# MCU.net
KiCad netlist of a schematic drawn in Altium Designer
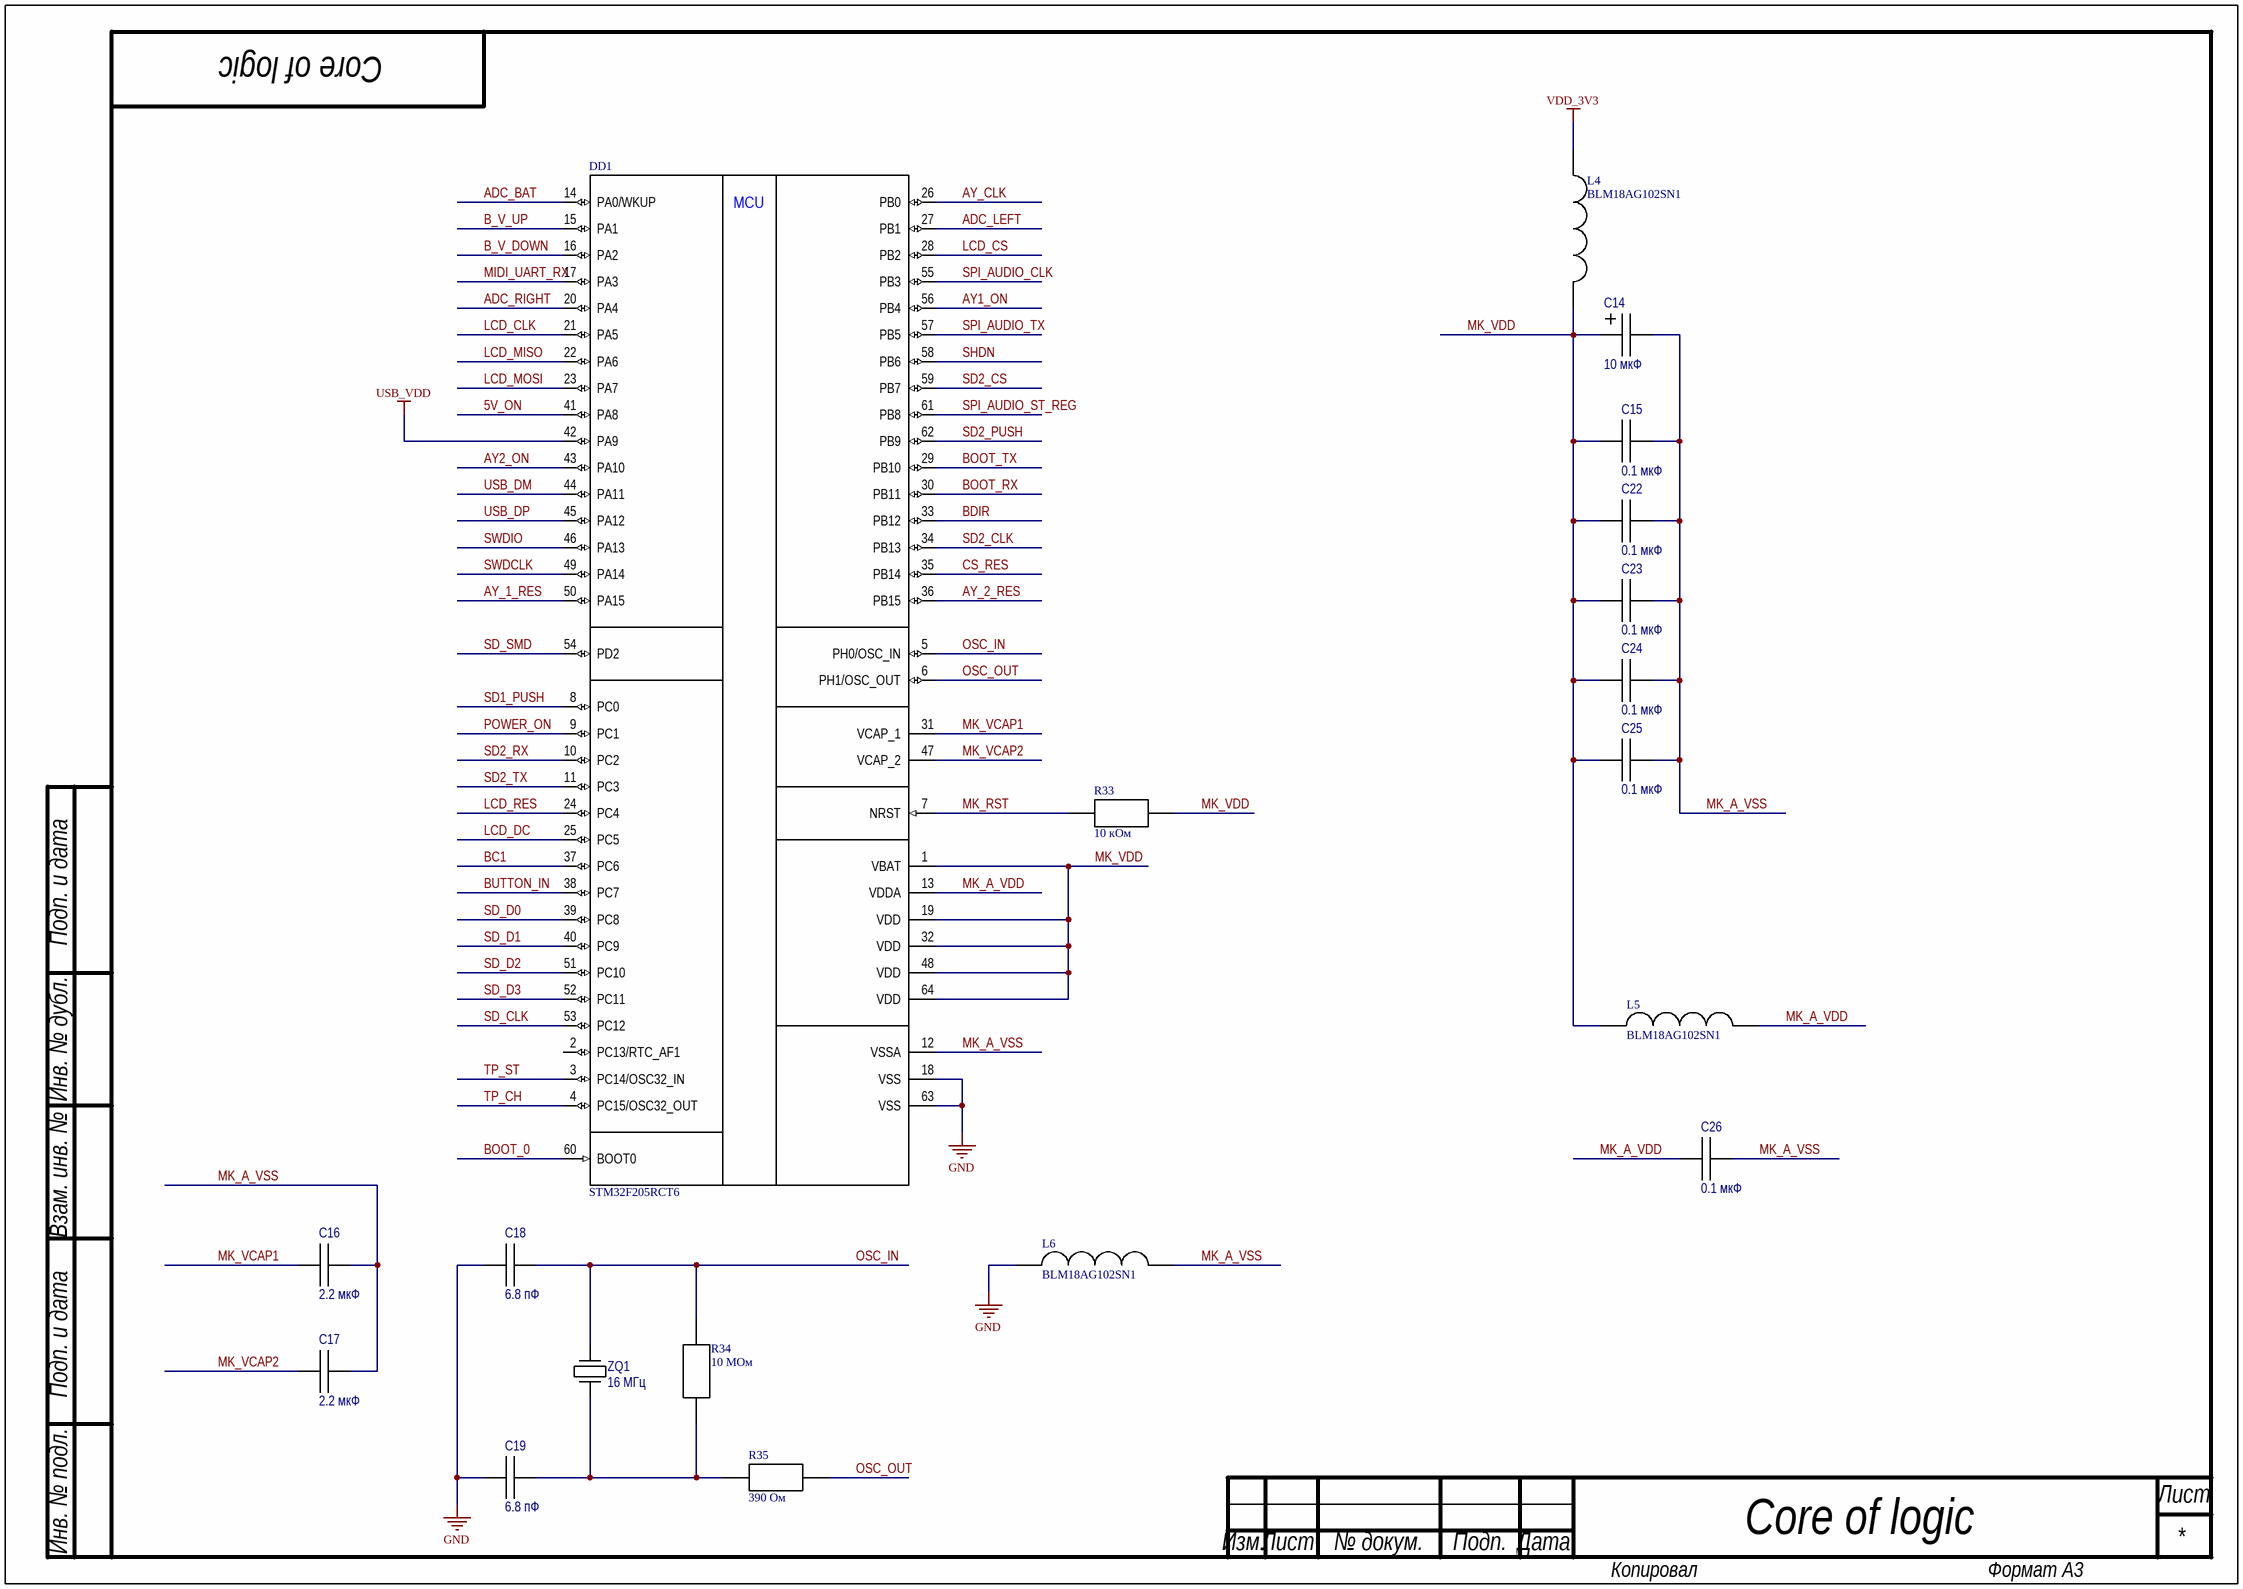
[diagram p0: MCU.SchDoc]

(export (version "E")
  (design (tool "Eeschema 10.0.6"))
  (components
    (comp (ref "C14")
      (value "10 мкФ")
      (footprint "C TAN_C")
      (description "SMD Tantalium Capacitor C")
      (fields
        (field (name "TOLERANCE") "/Укажите допуск в процентах/")
        (field (name "MANUFACTURER") "/Укажите компанию-производителя/")
      )
      (libsource (lib "my_lib") (part "CAP TAN_C"))
    )
    (comp (ref "C15")
      (value "0.1 мкФ")
      (footprint "C 1206")
      (description "SMD Capacitor 1206")
      (fields
        (field (name "TOLERANCE") "/Укажите допуск в процентах/")
        (field (name "MANUFACTURER") "/Укажите компанию-производителя/")
      )
      (libsource (lib "my_lib") (part "CAP 1206"))
    )
    (comp (ref "C16")
      (value "2.2 мкФ")
      (footprint "C 1206")
      (description "SMD Capacitor 1206")
      (fields
        (field (name "TOLERANCE") "/Укажите допуск в процентах/")
        (field (name "MANUFACTURER") "/Укажите компанию-производителя/")
      )
      (libsource (lib "my_lib") (part "CAP 1206"))
    )
    (comp (ref "C17")
      (value "2.2 мкФ")
      (footprint "C 1206")
      (description "SMD Capacitor 1206")
      (fields
        (field (name "TOLERANCE") "/Укажите допуск в процентах/")
        (field (name "MANUFACTURER") "/Укажите компанию-производителя/")
      )
      (libsource (lib "my_lib") (part "CAP 1206"))
    )
    (comp (ref "C18")
      (value "6.8 пФ")
      (footprint "C 1206")
      (description "SMD Capacitor 1206")
      (fields
        (field (name "TOLERANCE") "/Укажите допуск в процентах/")
        (field (name "MANUFACTURER") "/Укажите компанию-производителя/")
      )
      (libsource (lib "my_lib") (part "CAP 1206"))
    )
    (comp (ref "C19")
      (value "6.8 пФ")
      (footprint "C 1206")
      (description "SMD Capacitor 1206")
      (fields
        (field (name "TOLERANCE") "/Укажите допуск в процентах/")
        (field (name "MANUFACTURER") "/Укажите компанию-производителя/")
      )
      (libsource (lib "my_lib") (part "CAP 1206"))
    )
    (comp (ref "C22")
      (value "0.1 мкФ")
      (footprint "C 1206")
      (description "SMD Capacitor 1206")
      (fields
        (field (name "TOLERANCE") "/Укажите допуск в процентах/")
        (field (name "MANUFACTURER") "/Укажите компанию-производителя/")
      )
      (libsource (lib "my_lib") (part "CAP 1206"))
    )
    (comp (ref "C23")
      (value "0.1 мкФ")
      (footprint "C 1206")
      (description "SMD Capacitor 1206")
      (fields
        (field (name "TOLERANCE") "/Укажите допуск в процентах/")
        (field (name "MANUFACTURER") "/Укажите компанию-производителя/")
      )
      (libsource (lib "my_lib") (part "CAP 1206"))
    )
    (comp (ref "C24")
      (value "0.1 мкФ")
      (footprint "C 1206")
      (description "SMD Capacitor 1206")
      (fields
        (field (name "TOLERANCE") "/Укажите допуск в процентах/")
        (field (name "MANUFACTURER") "/Укажите компанию-производителя/")
      )
      (libsource (lib "my_lib") (part "CAP 1206"))
    )
    (comp (ref "C25")
      (value "0.1 мкФ")
      (footprint "C 1206")
      (description "SMD Capacitor 1206")
      (fields
        (field (name "TOLERANCE") "/Укажите допуск в процентах/")
        (field (name "MANUFACTURER") "/Укажите компанию-производителя/")
      )
      (libsource (lib "my_lib") (part "CAP 1206"))
    )
    (comp (ref "C26")
      (value "0.1 мкФ")
      (footprint "C 1206")
      (description "SMD Capacitor 1206")
      (fields
        (field (name "TOLERANCE") "/Укажите допуск в процентах/")
        (field (name "MANUFACTURER") "/Укажите компанию-производителя/")
      )
      (libsource (lib "my_lib") (part "CAP 1206"))
    )
    (comp (ref "DD1")
      (value "STM32F205RCT6")
      (footprint "LQFP64")
      (libsource (lib "my_lib") (part "STM32F205RCT6"))
    )
    (comp (ref "L4")
      (value "BLM18AG102SN1")
      (footprint "FB 0603")
      (libsource (lib "my_lib") (part "BLM18AG102SN1"))
    )
    (comp (ref "L5")
      (value "BLM18AG102SN1")
      (footprint "FB 0603")
      (libsource (lib "my_lib") (part "BLM18AG102SN1"))
    )
    (comp (ref "L6")
      (value "BLM18AG102SN1")
      (footprint "FB 0603")
      (libsource (lib "my_lib") (part "BLM18AG102SN1"))
    )
    (comp (ref "R33") (value "10 кОм") (footprint "RES 0805") (libsource (lib "my_lib") (part "RES 0805")))
    (comp (ref "R34") (value "10 МОм") (footprint "RES 0805") (libsource (lib "my_lib") (part "RES 0805")))
    (comp (ref "R35") (value "390 Ом") (footprint "RES 0805") (libsource (lib "my_lib") (part "RES 0805")))
    (comp (ref "ZQ1")
      (value "16 МГц")
      (footprint "NX3225SA")
      (description "QUARTZ CRYSTAL")
      (fields (field (name "MANUFACTURER") "NDK") (field (name "Comment") "NX3225SA-16.000M-STD-CRS-2"))
      (libsource (lib "my_lib") (part "NX3225SA-16.000M-STD-CRS-2"))
    )
  )
  (nets
    (net (code "1") (name "/5V_ON") (class "Default")
      (node (ref "DD1") (pin "41") (pinfunction "PA8_41") (pintype "bidirectional"))
    )
    (net (code "2") (name "/ADC_BAT") (class "Default")
      (node (ref "DD1") (pin "14") (pinfunction "PA0/WKUP_14") (pintype "bidirectional"))
    )
    (net (code "3") (name "/ADC_LEFT") (class "Default")
      (node (ref "DD1") (pin "27") (pinfunction "PB1_27") (pintype "bidirectional"))
    )
    (net (code "4") (name "/ADC_RIGHT") (class "Default")
      (node (ref "DD1") (pin "20") (pinfunction "PA4_20") (pintype "bidirectional"))
    )
    (net (code "5") (name "/AY1_ON") (class "Default")
      (node (ref "DD1") (pin "56") (pinfunction "PB4_56") (pintype "bidirectional"))
    )
    (net (code "6") (name "/AY2_ON") (class "Default")
      (node (ref "DD1") (pin "43") (pinfunction "PA10_43") (pintype "bidirectional"))
    )
    (net (code "7") (name "/AY_1_RES") (class "Default")
      (node (ref "DD1") (pin "50") (pinfunction "PA15_50") (pintype "bidirectional"))
    )
    (net (code "8") (name "/AY_2_RES") (class "Default")
      (node (ref "DD1") (pin "36") (pinfunction "PB15_36") (pintype "bidirectional"))
    )
    (net (code "9") (name "/AY_CLK") (class "Default")
      (node (ref "DD1") (pin "26") (pinfunction "PB0_26") (pintype "bidirectional"))
    )
    (net (code "10") (name "/BC1") (class "Default")
      (node (ref "DD1") (pin "37") (pinfunction "PC6_37") (pintype "bidirectional"))
    )
    (net (code "11") (name "/BDIR") (class "Default")
      (node (ref "DD1") (pin "33") (pinfunction "PB12_33") (pintype "bidirectional"))
    )
    (net (code "12") (name "/BOOT_0") (class "Default")
      (node (ref "DD1") (pin "60") (pinfunction "BOOT0_60") (pintype "input"))
    )
    (net (code "13") (name "/BOOT_RX") (class "Default")
      (node (ref "DD1") (pin "30") (pinfunction "PB11_30") (pintype "bidirectional"))
    )
    (net (code "14") (name "/BOOT_TX") (class "Default")
      (node (ref "DD1") (pin "29") (pinfunction "PB10_29") (pintype "bidirectional"))
    )
    (net (code "15") (name "/BUTTON_IN") (class "Default")
      (node (ref "DD1") (pin "38") (pinfunction "PC7_38") (pintype "bidirectional"))
    )
    (net (code "16") (name "/B_V_DOWN") (class "Default")
      (node (ref "DD1") (pin "16") (pinfunction "PA2_16") (pintype "bidirectional"))
    )
    (net (code "17") (name "/B_V_UP") (class "Default")
      (node (ref "DD1") (pin "15") (pinfunction "PA1_15") (pintype "bidirectional"))
    )
    (net (code "18") (name "/CS_RES") (class "Default")
      (node (ref "DD1") (pin "35") (pinfunction "PB14_35") (pintype "bidirectional"))
    )
    (net (code "19") (name "/LCD_CLK") (class "Default")
      (node (ref "DD1") (pin "21") (pinfunction "PA5_21") (pintype "bidirectional"))
    )
    (net (code "20") (name "/LCD_CS") (class "Default")
      (node (ref "DD1") (pin "28") (pinfunction "PB2_28") (pintype "bidirectional"))
    )
    (net (code "21") (name "/LCD_DC") (class "Default")
      (node (ref "DD1") (pin "25") (pinfunction "PC5_25") (pintype "bidirectional"))
    )
    (net (code "22") (name "/LCD_MISO") (class "Default")
      (node (ref "DD1") (pin "22") (pinfunction "PA6_22") (pintype "bidirectional"))
    )
    (net (code "23") (name "/LCD_MOSI") (class "Default")
      (node (ref "DD1") (pin "23") (pinfunction "PA7_23") (pintype "bidirectional"))
    )
    (net (code "24") (name "/LCD_RES") (class "Default")
      (node (ref "DD1") (pin "24") (pinfunction "PC4_24") (pintype "bidirectional"))
    )
    (net (code "25") (name "/MIDI_UART_RX") (class "Default")
      (node (ref "DD1") (pin "17") (pinfunction "PA3_17") (pintype "bidirectional"))
    )
    (net (code "26") (name "/MK_A_VDD") (class "Default")
      (node (ref "C26") (pin "1") (pinfunction "1_1") (pintype "passive"))
      (node (ref "DD1") (pin "13") (pinfunction "VDDA_13") (pintype "power_in"))
      (node (ref "L5") (pin "2") (pinfunction "2_2") (pintype "passive"))
    )
    (net (code "27") (name "/MK_A_VSS") (class "Default")
      (node (ref "C14") (pin "2") (pinfunction "2_2") (pintype "passive"))
      (node (ref "C15") (pin "2") (pinfunction "2_2") (pintype "passive"))
      (node (ref "C16") (pin "2") (pinfunction "2_2") (pintype "passive"))
      (node (ref "C17") (pin "2") (pinfunction "2_2") (pintype "passive"))
      (node (ref "C22") (pin "2") (pinfunction "2_2") (pintype "passive"))
      (node (ref "C23") (pin "2") (pinfunction "2_2") (pintype "passive"))
      (node (ref "C24") (pin "2") (pinfunction "2_2") (pintype "passive"))
      (node (ref "C25") (pin "2") (pinfunction "2_2") (pintype "passive"))
      (node (ref "C26") (pin "2") (pinfunction "2_2") (pintype "passive"))
      (node (ref "DD1") (pin "12") (pinfunction "VSSA_12") (pintype "power_in"))
      (node (ref "L6") (pin "2") (pinfunction "2_2") (pintype "passive"))
    )
    (net (code "28") (name "/MK_RST") (class "Default")
      (node (ref "DD1") (pin "7") (pinfunction "NRST_7") (pintype "input"))
      (node (ref "R33") (pin "1") (pinfunction "1_1") (pintype "passive"))
    )
    (net (code "29") (name "/MK_VCAP1") (class "Default")
      (node (ref "C16") (pin "1") (pinfunction "1_1") (pintype "passive"))
      (node (ref "DD1") (pin "31") (pinfunction "VCAP_1_31") (pintype "power_in"))
    )
    (net (code "30") (name "/MK_VCAP2") (class "Default")
      (node (ref "C17") (pin "1") (pinfunction "1_1") (pintype "passive"))
      (node (ref "DD1") (pin "47") (pinfunction "VCAP_2_47") (pintype "power_in"))
    )
    (net (code "31") (name "/MK_VDD") (class "Default")
      (node (ref "C14") (pin "1") (pinfunction "1_1") (pintype "passive"))
      (node (ref "C15") (pin "1") (pinfunction "1_1") (pintype "passive"))
      (node (ref "C22") (pin "1") (pinfunction "1_1") (pintype "passive"))
      (node (ref "C23") (pin "1") (pinfunction "1_1") (pintype "passive"))
      (node (ref "C24") (pin "1") (pinfunction "1_1") (pintype "passive"))
      (node (ref "C25") (pin "1") (pinfunction "1_1") (pintype "passive"))
      (node (ref "DD1") (pin "1") (pinfunction "VBAT_1") (pintype "power_in"))
      (node (ref "DD1") (pin "19") (pinfunction "VDD_19") (pintype "power_in"))
      (node (ref "DD1") (pin "32") (pinfunction "VDD_32") (pintype "power_in"))
      (node (ref "DD1") (pin "48") (pinfunction "VDD_48") (pintype "power_in"))
      (node (ref "DD1") (pin "64") (pinfunction "VDD_64") (pintype "power_in"))
      (node (ref "L4") (pin "2") (pinfunction "2_2") (pintype "passive"))
      (node (ref "L5") (pin "1") (pinfunction "1_1") (pintype "passive"))
      (node (ref "R33") (pin "2") (pinfunction "2_2") (pintype "passive"))
    )
    (net (code "32") (name "/OSC_IN") (class "Default")
      (node (ref "C18") (pin "2") (pinfunction "2_2") (pintype "passive"))
      (node (ref "DD1") (pin "5") (pinfunction "PH0/OSC_IN_5") (pintype "bidirectional"))
      (node (ref "R34") (pin "2") (pinfunction "2_2") (pintype "passive"))
      (node (ref "ZQ1") (pin "3") (pinfunction "XO_3") (pintype "passive"))
    )
    (net (code "33") (name "/OSC_OUT") (class "Default")
      (node (ref "DD1") (pin "6") (pinfunction "PH1/OSC_OUT_6") (pintype "bidirectional"))
      (node (ref "R35") (pin "2") (pinfunction "2_2") (pintype "passive"))
    )
    (net (code "34") (name "/POWER_ON") (class "Default")
      (node (ref "DD1") (pin "9") (pinfunction "PC1_9") (pintype "bidirectional"))
    )
    (net (code "35") (name "/SD1_PUSH") (class "Default")
      (node (ref "DD1") (pin "8") (pinfunction "PC0_8") (pintype "bidirectional"))
    )
    (net (code "36") (name "/SD2_CLK") (class "Default")
      (node (ref "DD1") (pin "34") (pinfunction "PB13_34") (pintype "bidirectional"))
    )
    (net (code "37") (name "/SD2_CS") (class "Default")
      (node (ref "DD1") (pin "59") (pinfunction "PB7_59") (pintype "bidirectional"))
    )
    (net (code "38") (name "/SD2_PUSH") (class "Default")
      (node (ref "DD1") (pin "62") (pinfunction "PB9_62") (pintype "bidirectional"))
    )
    (net (code "39") (name "/SD2_RX") (class "Default")
      (node (ref "DD1") (pin "10") (pinfunction "PC2_10") (pintype "bidirectional"))
    )
    (net (code "40") (name "/SD2_TX") (class "Default")
      (node (ref "DD1") (pin "11") (pinfunction "PC3_11") (pintype "bidirectional"))
    )
    (net (code "41") (name "/SD_CLK") (class "Default")
      (node (ref "DD1") (pin "53") (pinfunction "PC12_53") (pintype "bidirectional"))
    )
    (net (code "42") (name "/SD_D0") (class "Default")
      (node (ref "DD1") (pin "39") (pinfunction "PC8_39") (pintype "bidirectional"))
    )
    (net (code "43") (name "/SD_D1") (class "Default")
      (node (ref "DD1") (pin "40") (pinfunction "PC9_40") (pintype "bidirectional"))
    )
    (net (code "44") (name "/SD_D2") (class "Default")
      (node (ref "DD1") (pin "51") (pinfunction "PC10_51") (pintype "bidirectional"))
    )
    (net (code "45") (name "/SD_D3") (class "Default")
      (node (ref "DD1") (pin "52") (pinfunction "PC11_52") (pintype "bidirectional"))
    )
    (net (code "46") (name "/SD_SMD") (class "Default")
      (node (ref "DD1") (pin "54") (pinfunction "PD2_54") (pintype "bidirectional"))
    )
    (net (code "47") (name "/SHDN") (class "Default")
      (node (ref "DD1") (pin "58") (pinfunction "PB6_58") (pintype "bidirectional"))
    )
    (net (code "48") (name "/SPI_AUDIO_CLK") (class "Default")
      (node (ref "DD1") (pin "55") (pinfunction "PB3_55") (pintype "bidirectional"))
    )
    (net (code "49") (name "/SPI_AUDIO_ST_REG") (class "Default")
      (node (ref "DD1") (pin "61") (pinfunction "PB8_61") (pintype "bidirectional"))
    )
    (net (code "50") (name "/SPI_AUDIO_TX") (class "Default")
      (node (ref "DD1") (pin "57") (pinfunction "PB5_57") (pintype "bidirectional"))
    )
    (net (code "51") (name "/SWDCLK") (class "Default")
      (node (ref "DD1") (pin "49") (pinfunction "PA14_49") (pintype "bidirectional"))
    )
    (net (code "52") (name "/SWDIO") (class "Default")
      (node (ref "DD1") (pin "46") (pinfunction "PA13_46") (pintype "bidirectional"))
    )
    (net (code "53") (name "/TP_CH") (class "Default")
      (node (ref "DD1") (pin "4") (pinfunction "PC15/OSC32_OUT_4") (pintype "bidirectional"))
    )
    (net (code "54") (name "/TP_ST") (class "Default")
      (node (ref "DD1") (pin "3") (pinfunction "PC14/OSC32_IN_3") (pintype "bidirectional"))
    )
    (net (code "55") (name "/USB_DM") (class "Default")
      (node (ref "DD1") (pin "44") (pinfunction "PA11_44") (pintype "bidirectional"))
    )
    (net (code "56") (name "/USB_DP") (class "Default")
      (node (ref "DD1") (pin "45") (pinfunction "PA12_45") (pintype "bidirectional"))
    )
    (net (code "57") (name "GND") (class "Default")
      (node (ref "C18") (pin "1") (pinfunction "1_1") (pintype "passive"))
      (node (ref "C19") (pin "1") (pinfunction "1_1") (pintype "passive"))
      (node (ref "DD1") (pin "18") (pinfunction "VSS_18") (pintype "power_in"))
      (node (ref "DD1") (pin "63") (pinfunction "VSS_63") (pintype "power_in"))
      (node (ref "L6") (pin "1") (pinfunction "1_1") (pintype "passive"))
    )
    (net (code "58") (name "Net-(ZQ1-XI)") (class "Default")
      (node (ref "C19") (pin "2") (pinfunction "2_2") (pintype "passive"))
      (node (ref "R34") (pin "1") (pinfunction "1_1") (pintype "passive"))
      (node (ref "R35") (pin "1") (pinfunction "1_1") (pintype "passive"))
      (node (ref "ZQ1") (pin "1") (pinfunction "XI_1") (pintype "passive"))
    )
    (net (code "59") (name "USB_VDD") (class "Default")
      (node (ref "DD1") (pin "42") (pinfunction "PA9_42") (pintype "bidirectional"))
    )
    (net (code "60") (name "VDD_3V3") (class "Default")
      (node (ref "L4") (pin "1") (pinfunction "1_1") (pintype "passive"))
    )
    (net (code "61") (name "unconnected-(DD1-PC13{slash}RTC_AF1-Pad2)") (class "Default")
      (node (ref "DD1") (pin "2") (pinfunction "PC13/RTC_AF1_2") (pintype "bidirectional"))
    )
    (net (code "62") (name "unconnected-(ZQ1-NC-Pad2)") (class "Default")
      (node (ref "ZQ1") (pin "2") (pinfunction "NC_2") (pintype "passive"))
    )
    (net (code "63") (name "unconnected-(ZQ1-NC-Pad4)") (class "Default")
      (node (ref "ZQ1") (pin "4") (pinfunction "NC_4") (pintype "passive"))
    )
  )
)
